# CommunicationShield.net
KiCad netlist of a schematic drawn in EAGLE
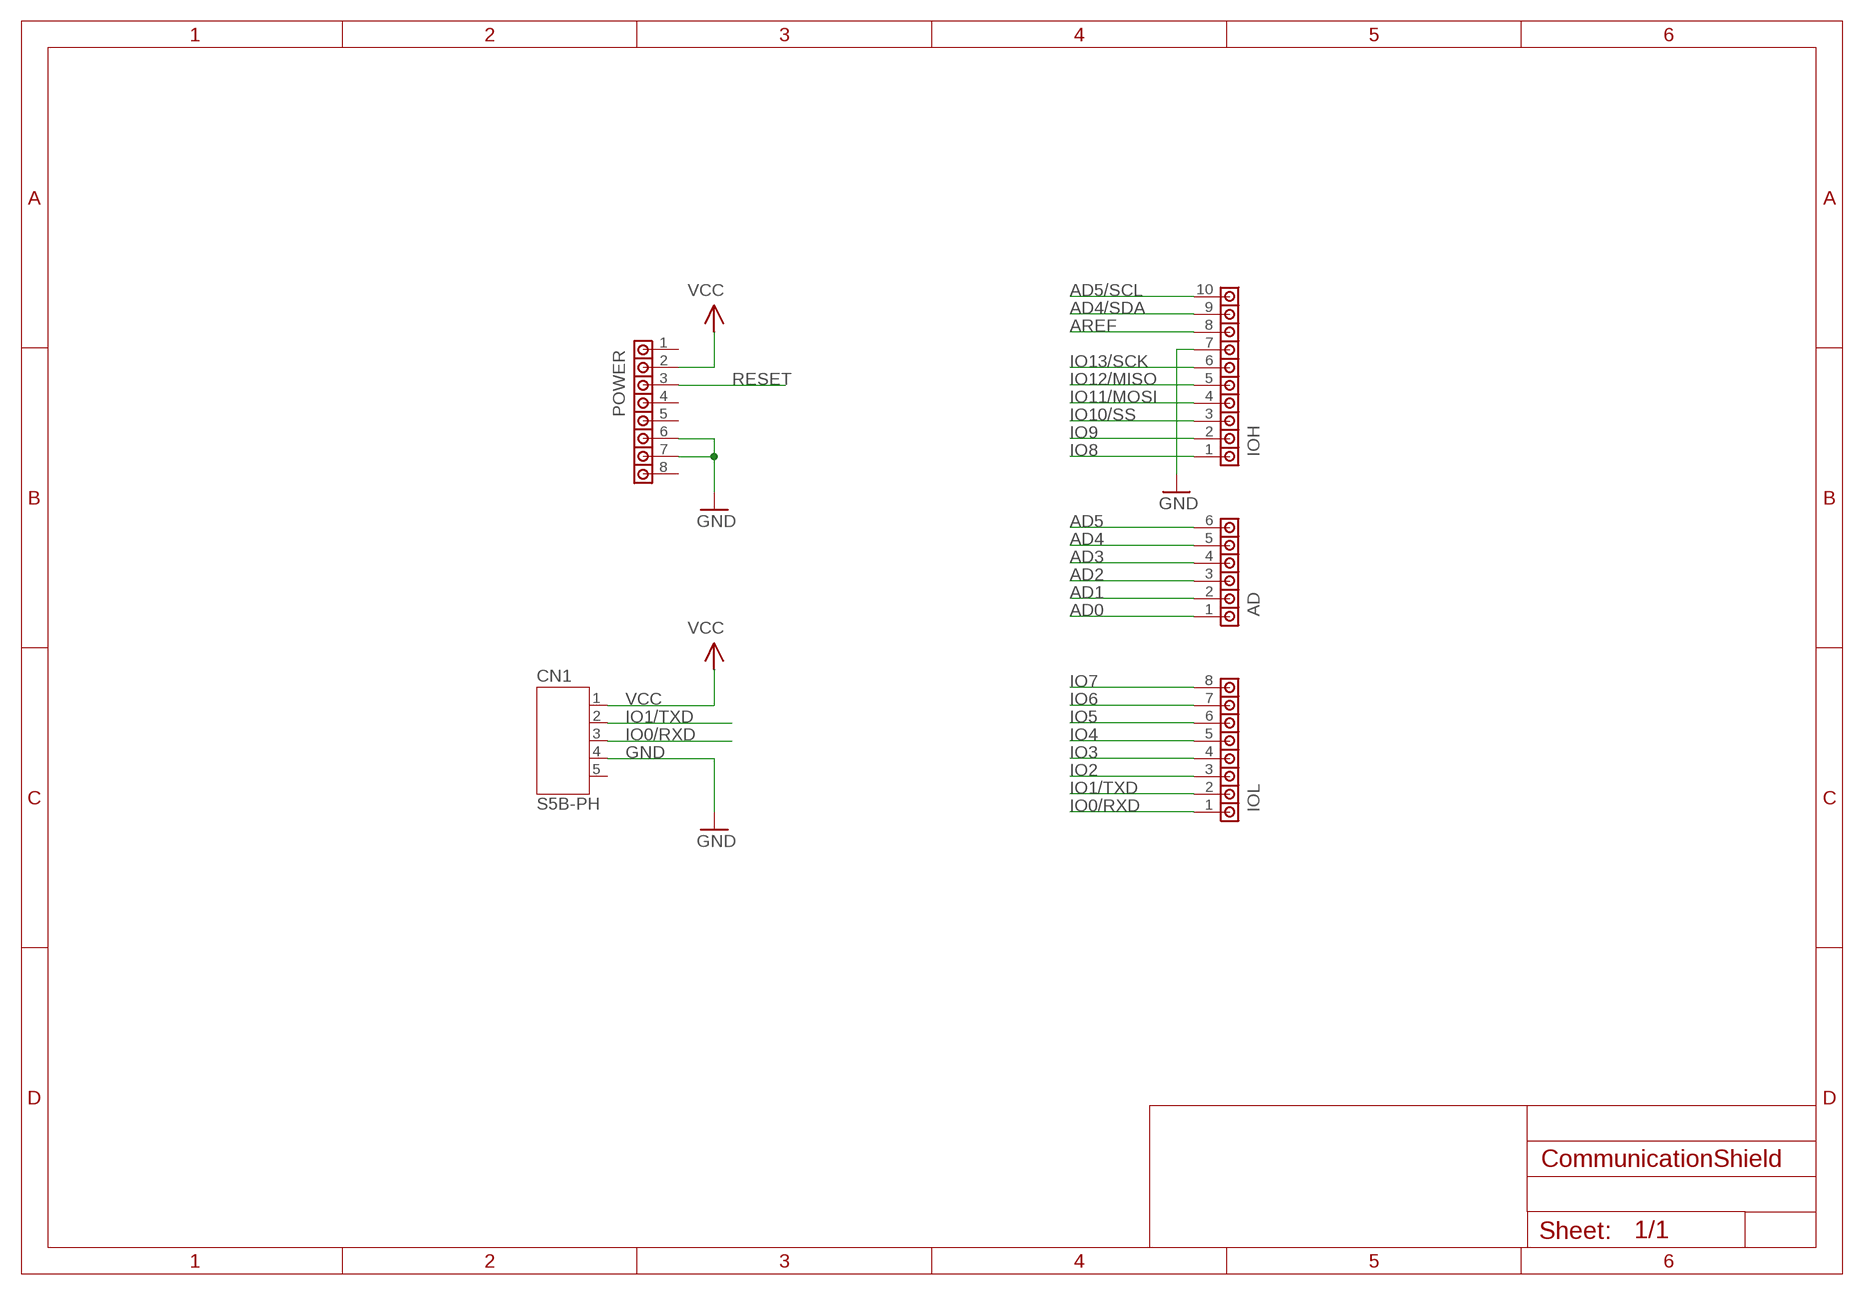
[diagram p0: schematic, sheet 1]

(export (version "E")
  (design (tool "Eeschema 10.0.6"))
  (components
    (comp (ref "AD")
      (value "PINHD-1X6")
      (footprint "eagle-import:PINHD-1X6")
      (libsource (lib "eagle-import") (part "PINHD-1X6"))
    )
    (comp (ref "CN1")
      (value "S5B-PH")
      (footprint "eagle-import:S5B-PH")
      (libsource (lib "eagle-import") (part "S5B-PH"))
    )
    (comp (ref "IOH")
      (value "PINHD-1X10")
      (footprint "eagle-import:PINHD-1X10")
      (libsource (lib "eagle-import") (part "PINHD-1X10"))
    )
    (comp (ref "IOL")
      (value "PINHD-1X8")
      (footprint "eagle-import:PINHD-1X8")
      (libsource (lib "eagle-import") (part "PINHD-1X8"))
    )
    (comp (ref "POWER")
      (value "PINHD-1X8")
      (footprint "eagle-import:PINHD-1X8")
      (libsource (lib "eagle-import") (part "PINHD-1X8"))
    )
  )
  (nets
    (net (code "1") (name "/AD0") (class "Default")
      (node (ref "AD") (pin "1") (pinfunction "1_1") (pintype "passive"))
    )
    (net (code "2") (name "/AD1") (class "Default")
      (node (ref "AD") (pin "2") (pinfunction "2_2") (pintype "passive"))
    )
    (net (code "3") (name "/AD2") (class "Default")
      (node (ref "AD") (pin "3") (pinfunction "3_3") (pintype "passive"))
    )
    (net (code "4") (name "/AD3") (class "Default")
      (node (ref "AD") (pin "4") (pinfunction "4_4") (pintype "passive"))
    )
    (net (code "5") (name "/AD4") (class "Default")
      (node (ref "AD") (pin "5") (pinfunction "5_5") (pintype "passive"))
    )
    (net (code "6") (name "/AD4{slash}SDA") (class "Default")
      (node (ref "IOH") (pin "9") (pinfunction "9_9") (pintype "passive"))
    )
    (net (code "7") (name "/AD5") (class "Default")
      (node (ref "AD") (pin "6") (pinfunction "6_6") (pintype "passive"))
    )
    (net (code "8") (name "/AD5{slash}SCL") (class "Default")
      (node (ref "IOH") (pin "10") (pinfunction "10_10") (pintype "passive"))
    )
    (net (code "9") (name "/AREF") (class "Default")
      (node (ref "IOH") (pin "8") (pinfunction "8_8") (pintype "passive"))
    )
    (net (code "10") (name "/IO0{slash}RXD") (class "Default")
      (node (ref "CN1") (pin "3") (pinfunction "3_3") (pintype "passive"))
      (node (ref "IOL") (pin "1") (pinfunction "1_1") (pintype "passive"))
    )
    (net (code "11") (name "/IO1{slash}TXD") (class "Default")
      (node (ref "CN1") (pin "2") (pinfunction "2_2") (pintype "passive"))
      (node (ref "IOL") (pin "2") (pinfunction "2_2") (pintype "passive"))
    )
    (net (code "12") (name "/IO2") (class "Default")
      (node (ref "IOL") (pin "3") (pinfunction "3_3") (pintype "passive"))
    )
    (net (code "13") (name "/IO3") (class "Default")
      (node (ref "IOL") (pin "4") (pinfunction "4_4") (pintype "passive"))
    )
    (net (code "14") (name "/IO4") (class "Default")
      (node (ref "IOL") (pin "5") (pinfunction "5_5") (pintype "passive"))
    )
    (net (code "15") (name "/IO5") (class "Default")
      (node (ref "IOL") (pin "6") (pinfunction "6_6") (pintype "passive"))
    )
    (net (code "16") (name "/IO6") (class "Default")
      (node (ref "IOL") (pin "7") (pinfunction "7_7") (pintype "passive"))
    )
    (net (code "17") (name "/IO7") (class "Default")
      (node (ref "IOL") (pin "8") (pinfunction "8_8") (pintype "passive"))
    )
    (net (code "18") (name "/IO8") (class "Default")
      (node (ref "IOH") (pin "1") (pinfunction "1_1") (pintype "passive"))
    )
    (net (code "19") (name "/IO9") (class "Default")
      (node (ref "IOH") (pin "2") (pinfunction "2_2") (pintype "passive"))
    )
    (net (code "20") (name "/IO10{slash}SS") (class "Default")
      (node (ref "IOH") (pin "3") (pinfunction "3_3") (pintype "passive"))
    )
    (net (code "21") (name "/IO11{slash}MOSI") (class "Default")
      (node (ref "IOH") (pin "4") (pinfunction "4_4") (pintype "passive"))
    )
    (net (code "22") (name "/IO12{slash}MISO") (class "Default")
      (node (ref "IOH") (pin "5") (pinfunction "5_5") (pintype "passive"))
    )
    (net (code "23") (name "/IO13{slash}SCK") (class "Default")
      (node (ref "IOH") (pin "6") (pinfunction "6_6") (pintype "passive"))
    )
    (net (code "24") (name "/RESET") (class "Default")
      (node (ref "POWER") (pin "3") (pinfunction "3_3") (pintype "passive"))
    )
    (net (code "25") (name "GND") (class "Default")
      (node (ref "CN1") (pin "4") (pinfunction "4_4") (pintype "passive"))
      (node (ref "IOH") (pin "7") (pinfunction "7_7") (pintype "passive"))
      (node (ref "POWER") (pin "6") (pinfunction "6_6") (pintype "passive"))
      (node (ref "POWER") (pin "7") (pinfunction "7_7") (pintype "passive"))
    )
    (net (code "26") (name "VCC") (class "Default")
      (node (ref "CN1") (pin "1") (pinfunction "1_1") (pintype "passive"))
      (node (ref "POWER") (pin "2") (pinfunction "2_2") (pintype "passive"))
    )
    (net (code "27") (name "unconnected-(CN1-Pad5)") (class "Default")
      (node (ref "CN1") (pin "5") (pinfunction "5_5") (pintype "passive"))
    )
    (net (code "28") (name "unconnected-(POWER-Pad1)") (class "Default")
      (node (ref "POWER") (pin "1") (pinfunction "1_1") (pintype "passive"))
    )
    (net (code "29") (name "unconnected-(POWER-Pad4)") (class "Default")
      (node (ref "POWER") (pin "4") (pinfunction "4_4") (pintype "passive"))
    )
    (net (code "30") (name "unconnected-(POWER-Pad5)") (class "Default")
      (node (ref "POWER") (pin "5") (pinfunction "5_5") (pintype "passive"))
    )
    (net (code "31") (name "unconnected-(POWER-Pad8)") (class "Default")
      (node (ref "POWER") (pin "8") (pinfunction "8_8") (pintype "passive"))
    )
  )
)
